# Power.net
KiCad netlist of a schematic drawn in Altium Designer
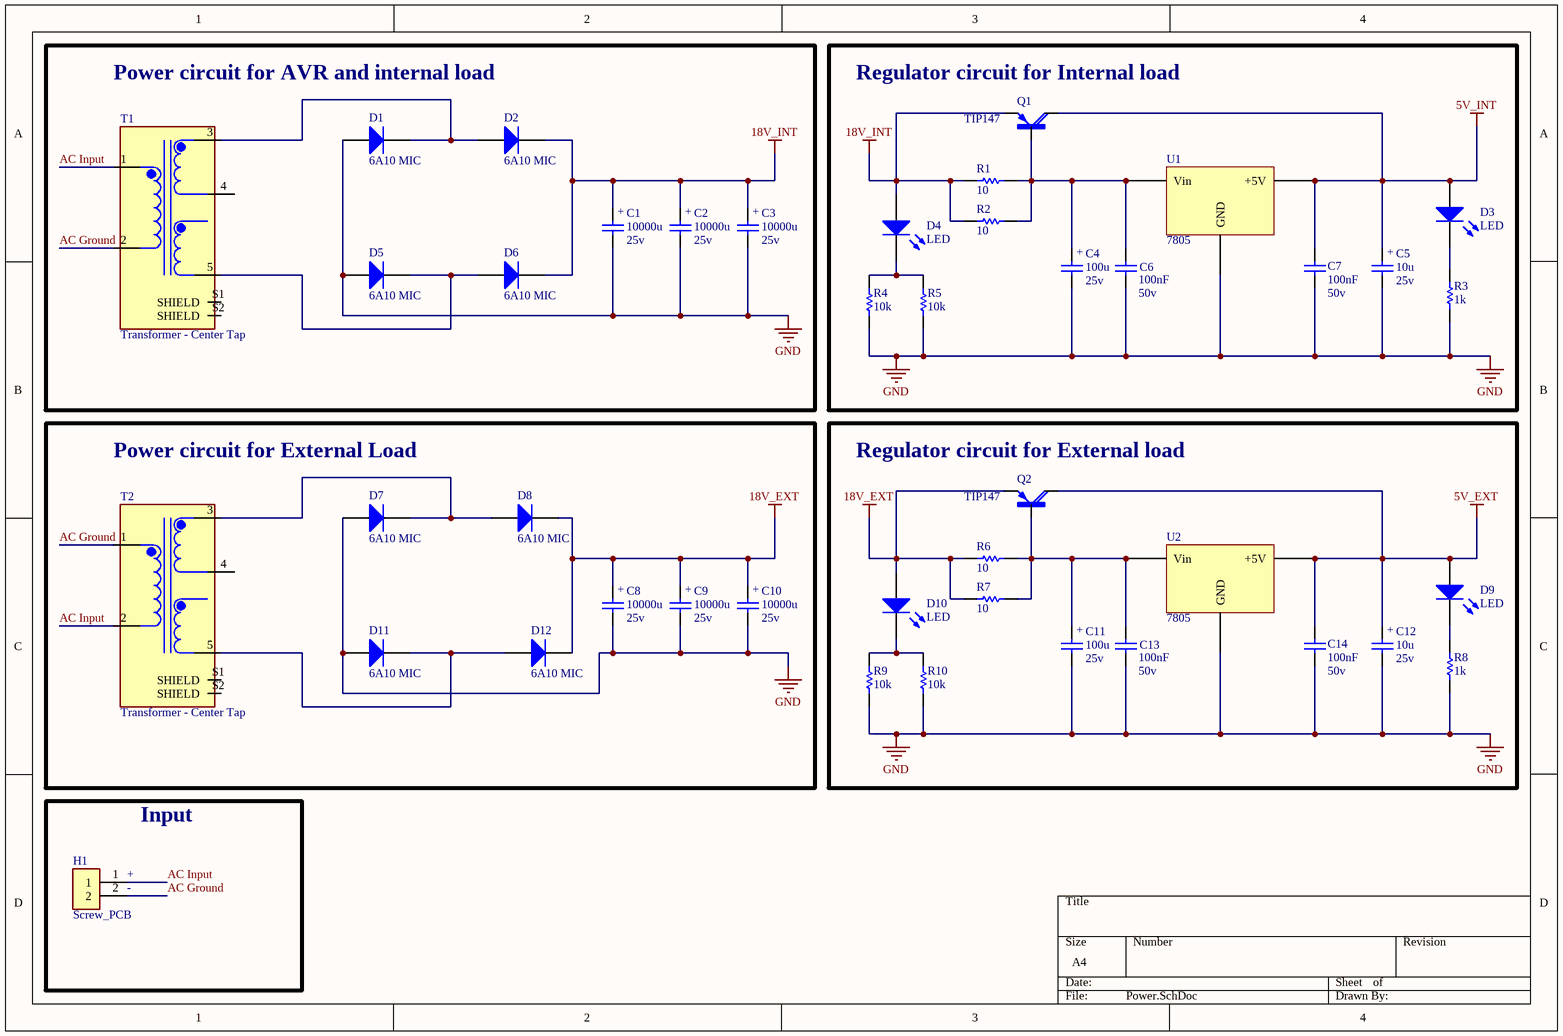
[diagram p0: Power.SchDoc]

(export (version "E")
  (design (tool "Eeschema 10.0.6"))
  (components
    (comp (ref "C1")
      (value "10000u")
      (footprint "MY_E7.5-16mm")
      (description "Polar capacitor")
      (fields (field (name "ASID PART NUMBER") "C-AS") (field (name "VOLTE") "25v"))
      (libsource (lib "Mylib+Rev+4") (part "Cap Pol"))
    )
    (comp (ref "C2")
      (value "10000u")
      (footprint "MY_E7.5-16mm")
      (description "Polar capacitor")
      (fields (field (name "ASID PART NUMBER") "C-AS") (field (name "VOLTE") "25v"))
      (libsource (lib "Mylib+Rev+4") (part "Cap Pol"))
    )
    (comp (ref "C3")
      (value "10000u")
      (footprint "MY_E7.5-16mm")
      (description "Polar capacitor")
      (fields (field (name "ASID PART NUMBER") "C-AS") (field (name "VOLTE") "25v"))
      (libsource (lib "Mylib+Rev+4") (part "Cap Pol"))
    )
    (comp (ref "C4")
      (value "100u")
      (footprint "MY_E2.5-5mm")
      (description "Polar capacitor")
      (fields (field (name "ASID PART NUMBER") "C-AS") (field (name "VOLTE") "25v"))
      (libsource (lib "Mylib+Rev+4") (part "Cap Pol"))
    )
    (comp (ref "C5")
      (value "10u")
      (footprint "MY_E2.5-5mm")
      (description "Polar capacitor")
      (fields (field (name "ASID PART NUMBER") "C-AS") (field (name "VOLTE") "25v"))
      (libsource (lib "Mylib+Rev+4") (part "Cap Pol"))
    )
    (comp (ref "C6")
      (value "100nF")
      (footprint "C0805")
      (description "None polar capacitor")
      (fields (field (name "ASID PART NUMBER") "C-AS") (field (name "VOLTE") "50v"))
      (libsource (lib "Mylib+Rev+4") (part "Cap ceramic"))
    )
    (comp (ref "C7")
      (value "100nF")
      (footprint "C0805")
      (description "None polar capacitor")
      (fields (field (name "ASID PART NUMBER") "C-AS") (field (name "VOLTE") "50v"))
      (libsource (lib "Mylib+Rev+4") (part "Cap ceramic"))
    )
    (comp (ref "C8")
      (value "10000u")
      (footprint "MY_E7.5-16mm")
      (description "Polar capacitor")
      (fields (field (name "ASID PART NUMBER") "C-AS") (field (name "VOLTE") "25v"))
      (libsource (lib "Mylib+Rev+4") (part "Cap Pol"))
    )
    (comp (ref "C9")
      (value "10000u")
      (footprint "MY_E7.5-16mm")
      (description "Polar capacitor")
      (fields (field (name "ASID PART NUMBER") "C-AS") (field (name "VOLTE") "25v"))
      (libsource (lib "Mylib+Rev+4") (part "Cap Pol"))
    )
    (comp (ref "C10")
      (value "10000u")
      (footprint "MY_E7.5-16mm")
      (description "Polar capacitor")
      (fields (field (name "ASID PART NUMBER") "C-AS") (field (name "VOLTE") "25v"))
      (libsource (lib "Mylib+Rev+4") (part "Cap Pol"))
    )
    (comp (ref "C11")
      (value "100u")
      (footprint "MY_E2.5-5mm")
      (description "Polar capacitor")
      (fields (field (name "ASID PART NUMBER") "C-AS") (field (name "VOLTE") "25v"))
      (libsource (lib "Mylib+Rev+4") (part "Cap Pol"))
    )
    (comp (ref "C12")
      (value "10u")
      (footprint "MY_E2.5-5mm")
      (description "Polar capacitor")
      (fields (field (name "ASID PART NUMBER") "C-AS") (field (name "VOLTE") "25v"))
      (libsource (lib "Mylib+Rev+4") (part "Cap Pol"))
    )
    (comp (ref "C13")
      (value "100nF")
      (footprint "C0805")
      (description "None polar capacitor")
      (fields (field (name "ASID PART NUMBER") "C-AS") (field (name "VOLTE") "50v"))
      (libsource (lib "Mylib+Rev+4") (part "Cap ceramic"))
    )
    (comp (ref "C14")
      (value "100nF")
      (footprint "C0805")
      (description "None polar capacitor")
      (fields (field (name "ASID PART NUMBER") "C-AS") (field (name "VOLTE") "50v"))
      (libsource (lib "Mylib+Rev+4") (part "Cap ceramic"))
    )
    (comp (ref "D1")
      (value "6A10 MIC")
      (footprint "R6_Axial")
      (description "1 Amp Diode")
      (fields (field (name "ASID PART NUMBER") "1n4007-AS"))
      (libsource (lib "Mylib+Rev+4") (part "1N4007"))
    )
    (comp (ref "D2")
      (value "6A10 MIC")
      (footprint "R6_Axial")
      (description "1 Amp Diode")
      (fields (field (name "ASID PART NUMBER") "1n4007-AS"))
      (libsource (lib "Mylib+Rev+4") (part "1N4007"))
    )
    (comp (ref "D3")
      (value "LED")
      (footprint "My_LED3MM")
      (description "Typical INFRARED GaAs LED")
      (fields (field (name "ASID PART NUMBER") "LED-AS"))
      (libsource (lib "Mylib+Rev+4") (part "LED"))
    )
    (comp (ref "D4")
      (value "LED")
      (footprint "My_LED3MM")
      (description "Typical INFRARED GaAs LED")
      (fields (field (name "ASID PART NUMBER") "LED-AS"))
      (libsource (lib "Mylib+Rev+4") (part "LED"))
    )
    (comp (ref "D5")
      (value "6A10 MIC")
      (footprint "R6_Axial")
      (description "1 Amp Diode")
      (fields (field (name "ASID PART NUMBER") "1n4007-AS"))
      (libsource (lib "Mylib+Rev+4") (part "1N4007"))
    )
    (comp (ref "D6")
      (value "6A10 MIC")
      (footprint "R6_Axial")
      (description "1 Amp Diode")
      (fields (field (name "ASID PART NUMBER") "1n4007-AS"))
      (libsource (lib "Mylib+Rev+4") (part "1N4007"))
    )
    (comp (ref "D7")
      (value "6A10 MIC")
      (footprint "R6_Axial")
      (description "1 Amp Diode")
      (fields (field (name "ASID PART NUMBER") "1n4007-AS"))
      (libsource (lib "Mylib+Rev+4") (part "1N4007"))
    )
    (comp (ref "D8")
      (value "6A10 MIC")
      (footprint "R6_Axial")
      (description "1 Amp Diode")
      (fields (field (name "ASID PART NUMBER") "1n4007-AS"))
      (libsource (lib "Mylib+Rev+4") (part "1N4007"))
    )
    (comp (ref "D9")
      (value "LED")
      (footprint "My_LED3MM")
      (description "Typical INFRARED GaAs LED")
      (fields (field (name "ASID PART NUMBER") "LED-AS"))
      (libsource (lib "Mylib+Rev+4") (part "LED"))
    )
    (comp (ref "D10")
      (value "LED")
      (footprint "My_LED3MM")
      (description "Typical INFRARED GaAs LED")
      (fields (field (name "ASID PART NUMBER") "LED-AS"))
      (libsource (lib "Mylib+Rev+4") (part "LED"))
    )
    (comp (ref "D11")
      (value "6A10 MIC")
      (footprint "R6_Axial")
      (description "1 Amp Diode")
      (fields (field (name "ASID PART NUMBER") "1n4007-AS"))
      (libsource (lib "Mylib+Rev+4") (part "1N4007"))
    )
    (comp (ref "D12")
      (value "6A10 MIC")
      (footprint "R6_Axial")
      (description "1 Amp Diode")
      (fields (field (name "ASID PART NUMBER") "1n4007-AS"))
      (libsource (lib "Mylib+Rev+4") (part "1N4007"))
    )
    (comp (ref "H1")
      (value "Screw_PCB")
      (footprint "Barrier_TB_8.26mm")
      (description "PCB to screw header")
      (fields (field (name "MF") "TE Connectivity") (field (name "MP") "282837-2"))
      (libsource (lib "Mylib+Rev+4") (part "Screw_PCB"))
    )
    (comp (ref "Q1")
      (value "TIP147")
      (footprint "SOT93")
      (description "Bipolar (BJT) Transistor PNP 100 V 10 A - 125 W Through Hole TO-218")
      (fields (field (name "MF") "NTE Electronics, Inc"))
      (libsource (lib "Mylib+Rev+4") (part "TIP147"))
    )
    (comp (ref "Q2")
      (value "TIP147")
      (footprint "SOT93")
      (description "Bipolar (BJT) Transistor PNP 100 V 10 A - 125 W Through Hole TO-218")
      (fields (field (name "MF") "NTE Electronics, Inc"))
      (libsource (lib "Mylib+Rev+4") (part "TIP147"))
    )
    (comp (ref "R1")
      (value "10")
      (footprint "MY_(2w)_0617_22")
      (description "Standard resistor")
      (fields (field (name "ASID PART NUMBER") "Res-AS"))
      (libsource (lib "Mylib+Rev+4") (part "Res"))
    )
    (comp (ref "R2")
      (value "10")
      (footprint "MY_(2w)_0617_22")
      (description "Standard resistor")
      (fields (field (name "ASID PART NUMBER") "Res-AS"))
      (libsource (lib "Mylib+Rev+4") (part "Res"))
    )
    (comp (ref "R3")
      (value "1k")
      (footprint "R0603")
      (description "Standard resistor")
      (fields (field (name "ASID PART NUMBER") "Res-AS"))
      (libsource (lib "Mylib+Rev+4") (part "Res"))
    )
    (comp (ref "R4")
      (value "10k")
      (footprint "R0603")
      (description "Standard resistor")
      (fields (field (name "ASID PART NUMBER") "Res-AS"))
      (libsource (lib "Mylib+Rev+4") (part "Res"))
    )
    (comp (ref "R5")
      (value "10k")
      (footprint "R0603")
      (description "Standard resistor")
      (fields (field (name "ASID PART NUMBER") "Res-AS"))
      (libsource (lib "Mylib+Rev+4") (part "Res"))
    )
    (comp (ref "R6")
      (value "10")
      (footprint "MY_(2w)_0617_22")
      (description "Standard resistor")
      (fields (field (name "ASID PART NUMBER") "Res-AS"))
      (libsource (lib "Mylib+Rev+4") (part "Res"))
    )
    (comp (ref "R7")
      (value "10")
      (footprint "MY_(2w)_0617_22")
      (description "Standard resistor")
      (fields (field (name "ASID PART NUMBER") "Res-AS"))
      (libsource (lib "Mylib+Rev+4") (part "Res"))
    )
    (comp (ref "R8")
      (value "1k")
      (footprint "R0603")
      (description "Standard resistor")
      (fields (field (name "ASID PART NUMBER") "Res-AS"))
      (libsource (lib "Mylib+Rev+4") (part "Res"))
    )
    (comp (ref "R9")
      (value "10k")
      (footprint "R0603")
      (description "Standard resistor")
      (fields (field (name "ASID PART NUMBER") "Res-AS"))
      (libsource (lib "Mylib+Rev+4") (part "Res"))
    )
    (comp (ref "R10")
      (value "10k")
      (footprint "R0603")
      (description "Standard resistor")
      (fields (field (name "ASID PART NUMBER") "Res-AS"))
      (libsource (lib "Mylib+Rev+4") (part "Res"))
    )
    (comp (ref "T1")
      (value "Transformer - Center Tap")
      (footprint "Transformer_CT")
      (description "Voltage - Primary 220V,Voltage - Secondary Parallel")
      (fields (field (name "MP") "F-151XP"))
      (libsource (lib "PCB_Project1") (part "Transformer - Center Tap"))
    )
    (comp (ref "T2")
      (value "Transformer - Center Tap")
      (footprint "Transformer_CT")
      (description "Voltage - Primary 220V,Voltage - Secondary Parallel")
      (fields (field (name "MP") "F-151XP"))
      (libsource (lib "PCB_Project1") (part "Transformer - Center Tap"))
    )
    (comp (ref "U1")
      (value "7805")
      (footprint "MY_TO220_Heatsink 2 TO-220 (20x14x9mm)")
      (description "Regulator")
      (fields (field (name "ASID PART NUMBER") "7805-AS"))
      (libsource (lib "Mylib+Rev+4") (part "7805"))
    )
    (comp (ref "U2")
      (value "7805")
      (footprint "MY_TO220_Heatsink 2 TO-220 (20x14x9mm)")
      (description "Regulator")
      (fields (field (name "ASID PART NUMBER") "7805-AS"))
      (libsource (lib "Mylib+Rev+4") (part "7805"))
    )
  )
  (nets
    (net (code "1") (name "/AC Ground") (class "Default")
      (node (ref "H1") (pin "2") (pinfunction "2_2") (pintype "passive"))
      (node (ref "T1") (pin "2") (pinfunction "2_2") (pintype "passive"))
      (node (ref "T2") (pin "1") (pinfunction "1_1") (pintype "passive"))
    )
    (net (code "2") (name "/AC Input") (class "Default")
      (node (ref "H1") (pin "1") (pinfunction "1_1") (pintype "passive"))
      (node (ref "T1") (pin "1") (pinfunction "1_1") (pintype "passive"))
      (node (ref "T2") (pin "2") (pinfunction "2_2") (pintype "passive"))
    )
    (net (code "3") (name "5V_EXT") (class "Default")
      (node (ref "C12") (pin "+") (pinfunction "+_+") (pintype "passive"))
      (node (ref "C14") (pin "2") (pinfunction "2_2") (pintype "passive"))
      (node (ref "D9") (pin "A") (pinfunction "A_A") (pintype "passive"))
      (node (ref "Q2") (pin "C") (pinfunction "C_C") (pintype "passive"))
      (node (ref "U2") (pin "3") (pinfunction "+5V_3") (pintype "power_in"))
    )
    (net (code "4") (name "5V_INT") (class "Default")
      (node (ref "C5") (pin "+") (pinfunction "+_+") (pintype "passive"))
      (node (ref "C7") (pin "2") (pinfunction "2_2") (pintype "passive"))
      (node (ref "D3") (pin "A") (pinfunction "A_A") (pintype "passive"))
      (node (ref "Q1") (pin "C") (pinfunction "C_C") (pintype "passive"))
      (node (ref "U1") (pin "3") (pinfunction "+5V_3") (pintype "power_in"))
    )
    (net (code "5") (name "18V_EXT") (class "Default")
      (node (ref "C10") (pin "+") (pinfunction "+_+") (pintype "passive"))
      (node (ref "C8") (pin "+") (pinfunction "+_+") (pintype "passive"))
      (node (ref "C9") (pin "+") (pinfunction "+_+") (pintype "passive"))
      (node (ref "D10") (pin "A") (pinfunction "A_A") (pintype "passive"))
      (node (ref "D12") (pin "K") (pinfunction "K_K") (pintype "passive"))
      (node (ref "D8") (pin "K") (pinfunction "K_K") (pintype "passive"))
      (node (ref "Q2") (pin "E") (pinfunction "E_E") (pintype "passive"))
      (node (ref "R6") (pin "1") (pinfunction "1_1") (pintype "passive"))
      (node (ref "R7") (pin "1") (pinfunction "1_1") (pintype "passive"))
    )
    (net (code "6") (name "18V_INT") (class "Default")
      (node (ref "C1") (pin "+") (pinfunction "+_+") (pintype "passive"))
      (node (ref "C2") (pin "+") (pinfunction "+_+") (pintype "passive"))
      (node (ref "C3") (pin "+") (pinfunction "+_+") (pintype "passive"))
      (node (ref "D2") (pin "K") (pinfunction "K_K") (pintype "passive"))
      (node (ref "D4") (pin "A") (pinfunction "A_A") (pintype "passive"))
      (node (ref "D6") (pin "K") (pinfunction "K_K") (pintype "passive"))
      (node (ref "Q1") (pin "E") (pinfunction "E_E") (pintype "passive"))
      (node (ref "R1") (pin "1") (pinfunction "1_1") (pintype "passive"))
      (node (ref "R2") (pin "1") (pinfunction "1_1") (pintype "passive"))
    )
    (net (code "7") (name "GND") (class "Default")
      (node (ref "C1") (pin "-") (pinfunction "-_-") (pintype "passive"))
      (node (ref "C10") (pin "-") (pinfunction "-_-") (pintype "passive"))
      (node (ref "C11") (pin "-") (pinfunction "-_-") (pintype "passive"))
      (node (ref "C12") (pin "-") (pinfunction "-_-") (pintype "passive"))
      (node (ref "C13") (pin "1") (pinfunction "1_1") (pintype "passive"))
      (node (ref "C14") (pin "1") (pinfunction "1_1") (pintype "passive"))
      (node (ref "C2") (pin "-") (pinfunction "-_-") (pintype "passive"))
      (node (ref "C3") (pin "-") (pinfunction "-_-") (pintype "passive"))
      (node (ref "C4") (pin "-") (pinfunction "-_-") (pintype "passive"))
      (node (ref "C5") (pin "-") (pinfunction "-_-") (pintype "passive"))
      (node (ref "C6") (pin "1") (pinfunction "1_1") (pintype "passive"))
      (node (ref "C7") (pin "1") (pinfunction "1_1") (pintype "passive"))
      (node (ref "C8") (pin "-") (pinfunction "-_-") (pintype "passive"))
      (node (ref "C9") (pin "-") (pinfunction "-_-") (pintype "passive"))
      (node (ref "D1") (pin "A") (pinfunction "A_A") (pintype "passive"))
      (node (ref "D11") (pin "A") (pinfunction "A_A") (pintype "passive"))
      (node (ref "D5") (pin "A") (pinfunction "A_A") (pintype "passive"))
      (node (ref "D7") (pin "A") (pinfunction "A_A") (pintype "passive"))
      (node (ref "R10") (pin "2") (pinfunction "2_2") (pintype "passive"))
      (node (ref "R3") (pin "2") (pinfunction "2_2") (pintype "passive"))
      (node (ref "R4") (pin "2") (pinfunction "2_2") (pintype "passive"))
      (node (ref "R5") (pin "2") (pinfunction "2_2") (pintype "passive"))
      (node (ref "R8") (pin "2") (pinfunction "2_2") (pintype "passive"))
      (node (ref "R9") (pin "2") (pinfunction "2_2") (pintype "passive"))
      (node (ref "U1") (pin "2") (pinfunction "GND_2") (pintype "power_in"))
      (node (ref "U2") (pin "2") (pinfunction "GND_2") (pintype "power_in"))
    )
    (net (code "8") (name "Net-(D1-PadK)") (class "Default")
      (node (ref "D1") (pin "K") (pinfunction "K_K") (pintype "passive"))
      (node (ref "D2") (pin "A") (pinfunction "A_A") (pintype "passive"))
      (node (ref "T1") (pin "3") (pinfunction "3_3") (pintype "passive"))
    )
    (net (code "9") (name "Net-(D3-PadK)") (class "Default")
      (node (ref "D3") (pin "K") (pinfunction "K_K") (pintype "passive"))
      (node (ref "R3") (pin "1") (pinfunction "1_1") (pintype "passive"))
    )
    (net (code "10") (name "Net-(D4-PadK)") (class "Default")
      (node (ref "D4") (pin "K") (pinfunction "K_K") (pintype "passive"))
      (node (ref "R4") (pin "1") (pinfunction "1_1") (pintype "passive"))
      (node (ref "R5") (pin "1") (pinfunction "1_1") (pintype "passive"))
    )
    (net (code "11") (name "Net-(D5-PadK)") (class "Default")
      (node (ref "D5") (pin "K") (pinfunction "K_K") (pintype "passive"))
      (node (ref "D6") (pin "A") (pinfunction "A_A") (pintype "passive"))
      (node (ref "T1") (pin "5") (pinfunction "5_5") (pintype "passive"))
    )
    (net (code "12") (name "Net-(D7-PadK)") (class "Default")
      (node (ref "D7") (pin "K") (pinfunction "K_K") (pintype "passive"))
      (node (ref "D8") (pin "A") (pinfunction "A_A") (pintype "passive"))
      (node (ref "T2") (pin "3") (pinfunction "3_3") (pintype "passive"))
    )
    (net (code "13") (name "Net-(D9-PadK)") (class "Default")
      (node (ref "D9") (pin "K") (pinfunction "K_K") (pintype "passive"))
      (node (ref "R8") (pin "1") (pinfunction "1_1") (pintype "passive"))
    )
    (net (code "14") (name "Net-(D10-PadK)") (class "Default")
      (node (ref "D10") (pin "K") (pinfunction "K_K") (pintype "passive"))
      (node (ref "R10") (pin "1") (pinfunction "1_1") (pintype "passive"))
      (node (ref "R9") (pin "1") (pinfunction "1_1") (pintype "passive"))
    )
    (net (code "15") (name "Net-(D11-PadK)") (class "Default")
      (node (ref "D11") (pin "K") (pinfunction "K_K") (pintype "passive"))
      (node (ref "D12") (pin "A") (pinfunction "A_A") (pintype "passive"))
      (node (ref "T2") (pin "5") (pinfunction "5_5") (pintype "passive"))
    )
    (net (code "16") (name "Net-(U1-Vin)") (class "Default")
      (node (ref "C4") (pin "+") (pinfunction "+_+") (pintype "passive"))
      (node (ref "C6") (pin "2") (pinfunction "2_2") (pintype "passive"))
      (node (ref "Q1") (pin "B") (pinfunction "B_B") (pintype "passive"))
      (node (ref "R1") (pin "2") (pinfunction "2_2") (pintype "passive"))
      (node (ref "R2") (pin "2") (pinfunction "2_2") (pintype "passive"))
      (node (ref "U1") (pin "1") (pinfunction "Vin_1") (pintype "power_in"))
    )
    (net (code "17") (name "Net-(U2-Vin)") (class "Default")
      (node (ref "C11") (pin "+") (pinfunction "+_+") (pintype "passive"))
      (node (ref "C13") (pin "2") (pinfunction "2_2") (pintype "passive"))
      (node (ref "Q2") (pin "B") (pinfunction "B_B") (pintype "passive"))
      (node (ref "R6") (pin "2") (pinfunction "2_2") (pintype "passive"))
      (node (ref "R7") (pin "2") (pinfunction "2_2") (pintype "passive"))
      (node (ref "U2") (pin "1") (pinfunction "Vin_1") (pintype "power_in"))
    )
    (net (code "18") (name "unconnected-(T1-Pad4)") (class "Default")
      (node (ref "T1") (pin "4") (pinfunction "4_4") (pintype "passive"))
    )
    (net (code "19") (name "unconnected-(T1-SHIELD-PadS1)") (class "Default")
      (node (ref "T1") (pin "S1") (pinfunction "SHIELD_S1") (pintype "passive"))
    )
    (net (code "20") (name "unconnected-(T1-SHIELD-PadS2)") (class "Default")
      (node (ref "T1") (pin "S2") (pinfunction "SHIELD_S2") (pintype "passive"))
    )
    (net (code "21") (name "unconnected-(T2-Pad4)") (class "Default")
      (node (ref "T2") (pin "4") (pinfunction "4_4") (pintype "passive"))
    )
    (net (code "22") (name "unconnected-(T2-SHIELD-PadS1)") (class "Default")
      (node (ref "T2") (pin "S1") (pinfunction "SHIELD_S1") (pintype "passive"))
    )
    (net (code "23") (name "unconnected-(T2-SHIELD-PadS2)") (class "Default")
      (node (ref "T2") (pin "S2") (pinfunction "SHIELD_S2") (pintype "passive"))
    )
  )
)
